# M420X.net
KiCad netlist of a schematic drawn in EAGLE
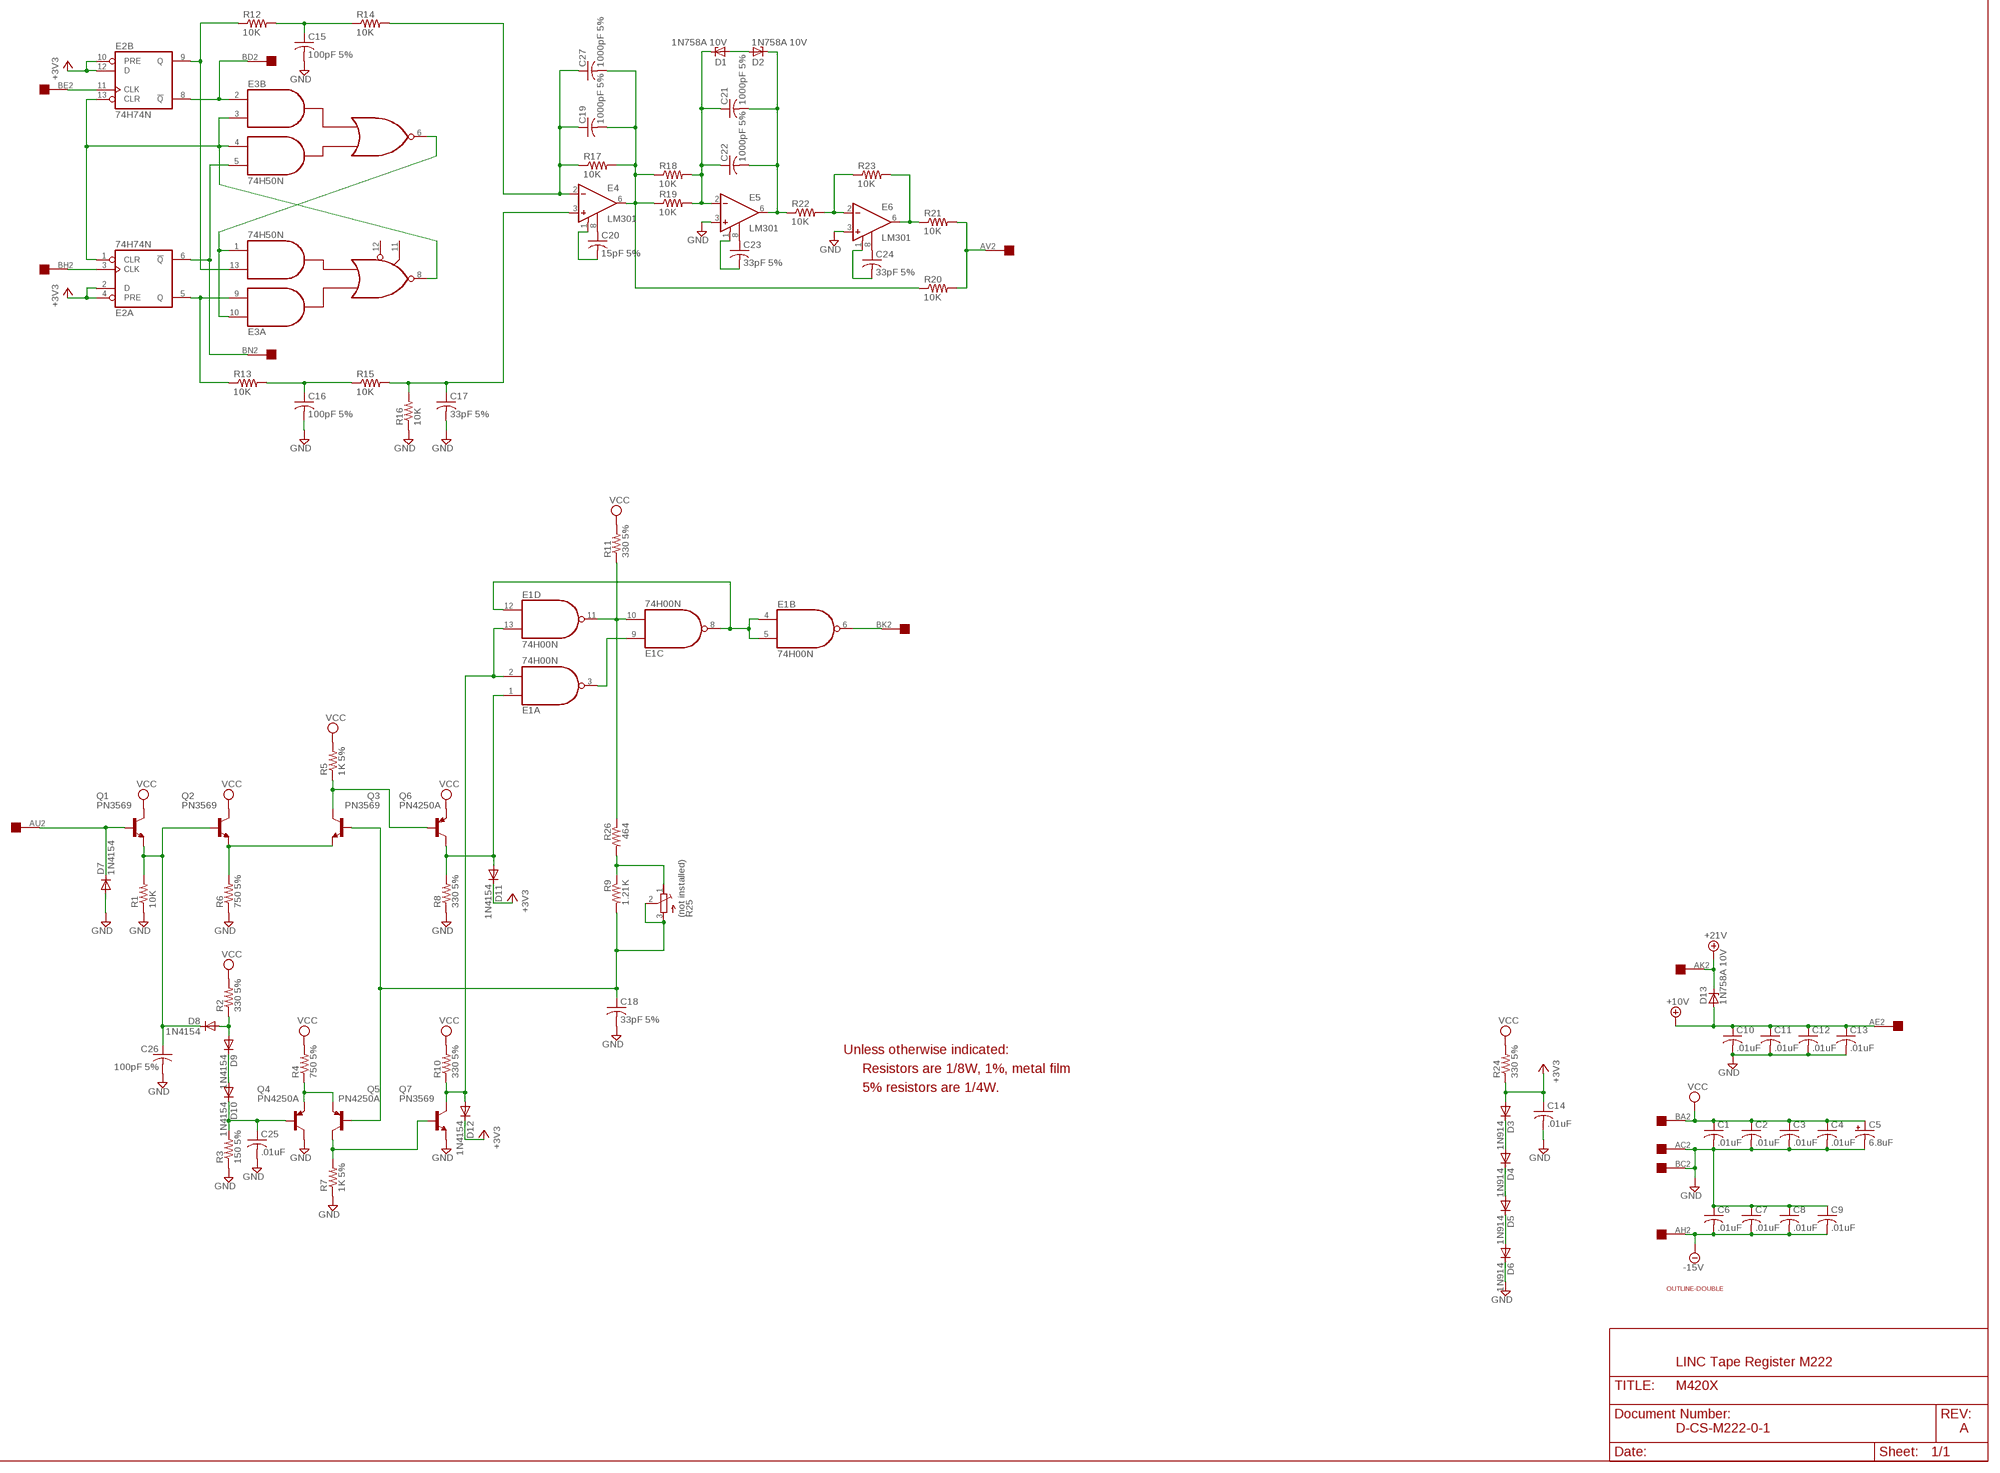
[diagram p0: schematic, sheet 1]

(export (version "E")
  (design (tool "Eeschema 10.0.6"))
  (components
    (comp (ref "C1")
      (value ".01uF")
      (footprint "eagle-import:C050-025X075")
      (libsource (lib "eagle-import") (part "C-US050-025X075"))
    )
    (comp (ref "C2")
      (value ".01uF")
      (footprint "eagle-import:C050-025X075")
      (libsource (lib "eagle-import") (part "C-US050-025X075"))
    )
    (comp (ref "C3")
      (value ".01uF")
      (footprint "eagle-import:C050-025X075")
      (libsource (lib "eagle-import") (part "C-US050-025X075"))
    )
    (comp (ref "C4")
      (value ".01uF")
      (footprint "eagle-import:C050-025X075")
      (libsource (lib "eagle-import") (part "C-US050-025X075"))
    )
    (comp (ref "C5")
      (value "6.8uF")
      (footprint "eagle-import:E12-8")
      (libsource (lib "eagle-import") (part "CPOL-USE20-8AXIAL"))
    )
    (comp (ref "C6")
      (value ".01uF")
      (footprint "eagle-import:C050-025X075")
      (libsource (lib "eagle-import") (part "C-US050-025X075"))
    )
    (comp (ref "C7")
      (value ".01uF")
      (footprint "eagle-import:C050-025X075")
      (libsource (lib "eagle-import") (part "C-US050-025X075"))
    )
    (comp (ref "C8")
      (value ".01uF")
      (footprint "eagle-import:C050-025X075")
      (libsource (lib "eagle-import") (part "C-US050-025X075"))
    )
    (comp (ref "C9")
      (value ".01uF")
      (footprint "eagle-import:C050-025X075")
      (libsource (lib "eagle-import") (part "C-US050-025X075"))
    )
    (comp (ref "C10")
      (value ".01uF")
      (footprint "eagle-import:C050-025X075")
      (libsource (lib "eagle-import") (part "C-US050-025X075"))
    )
    (comp (ref "C11")
      (value ".01uF")
      (footprint "eagle-import:C050-025X075")
      (libsource (lib "eagle-import") (part "C-US050-025X075"))
    )
    (comp (ref "C12")
      (value ".01uF")
      (footprint "eagle-import:C050-025X075")
      (libsource (lib "eagle-import") (part "C-US050-025X075"))
    )
    (comp (ref "C13")
      (value ".01uF")
      (footprint "eagle-import:C050-025X075")
      (libsource (lib "eagle-import") (part "C-US050-025X075"))
    )
    (comp (ref "C14")
      (value ".01uF")
      (footprint "eagle-import:C050-025X075")
      (libsource (lib "eagle-import") (part "C-US050-025X075"))
    )
    (comp (ref "C15")
      (value "100pF 5%")
      (footprint "eagle-import:C050-025X075")
      (libsource (lib "eagle-import") (part "C-US050-025X075"))
    )
    (comp (ref "C16")
      (value "100pF 5%")
      (footprint "eagle-import:C050-025X075")
      (libsource (lib "eagle-import") (part "C-US050-025X075"))
    )
    (comp (ref "C17")
      (value "33pF 5%")
      (footprint "eagle-import:C050-025X075")
      (libsource (lib "eagle-import") (part "C-US050-025X075"))
    )
    (comp (ref "C18")
      (value "33pF 5%")
      (footprint "eagle-import:C050-025X075")
      (libsource (lib "eagle-import") (part "C-US050-025X075"))
    )
    (comp (ref "C19")
      (value "1000pF 5%")
      (footprint "eagle-import:C050-025X075")
      (libsource (lib "eagle-import") (part "C-US050-025X075"))
    )
    (comp (ref "C20")
      (value "15pF 5%")
      (footprint "eagle-import:C050-025X075")
      (libsource (lib "eagle-import") (part "C-US050-025X075"))
    )
    (comp (ref "C21")
      (value "1000pF 5%")
      (footprint "eagle-import:C050-025X075")
      (libsource (lib "eagle-import") (part "C-US050-025X075"))
    )
    (comp (ref "C22")
      (value "1000pF 5%")
      (footprint "eagle-import:C050-025X075")
      (libsource (lib "eagle-import") (part "C-US050-025X075"))
    )
    (comp (ref "C23")
      (value "33pF 5%")
      (footprint "eagle-import:C050-025X075")
      (libsource (lib "eagle-import") (part "C-US050-025X075"))
    )
    (comp (ref "C24")
      (value "33pF 5%")
      (footprint "eagle-import:C050-025X075")
      (libsource (lib "eagle-import") (part "C-US050-025X075"))
    )
    (comp (ref "C25")
      (value ".01uF")
      (footprint "eagle-import:C050-025X075")
      (libsource (lib "eagle-import") (part "C-US050-025X075"))
    )
    (comp (ref "C26")
      (value "100pF 5%")
      (footprint "eagle-import:C050-025X075")
      (libsource (lib "eagle-import") (part "C-US050-025X075"))
    )
    (comp (ref "C27")
      (value "1000pF 5%")
      (footprint "eagle-import:C050-025X075")
      (libsource (lib "eagle-import") (part "C-US050-025X075"))
    )
    (comp (ref "D1")
      (value "1N758A 10V")
      (footprint "eagle-import:DO35Z10")
      (libsource (lib "eagle-import") (part "ZENER-DIODEDO35Z10"))
    )
    (comp (ref "D2")
      (value "1N758A 10V")
      (footprint "eagle-import:DO35Z10")
      (libsource (lib "eagle-import") (part "ZENER-DIODEDO35Z10"))
    )
    (comp (ref "D3")
      (value "1N914")
      (footprint "eagle-import:DO35-10")
      (libsource (lib "eagle-import") (part "1N4148DO35-10"))
    )
    (comp (ref "D4")
      (value "1N914")
      (footprint "eagle-import:DO35-10")
      (libsource (lib "eagle-import") (part "1N4148DO35-10"))
    )
    (comp (ref "D5")
      (value "1N914")
      (footprint "eagle-import:DO35-10")
      (libsource (lib "eagle-import") (part "1N4148DO35-10"))
    )
    (comp (ref "D6")
      (value "1N914")
      (footprint "eagle-import:DO35-10")
      (libsource (lib "eagle-import") (part "1N4148DO35-10"))
    )
    (comp (ref "D7")
      (value "1N4154")
      (footprint "eagle-import:DO35-10")
      (libsource (lib "eagle-import") (part "1N4148DO35-10"))
    )
    (comp (ref "D8")
      (value "1N4154")
      (footprint "eagle-import:DO35-10")
      (libsource (lib "eagle-import") (part "1N4148DO35-10"))
    )
    (comp (ref "D9")
      (value "1N4154")
      (footprint "eagle-import:DO35-10")
      (libsource (lib "eagle-import") (part "1N4148DO35-10"))
    )
    (comp (ref "D10")
      (value "1N4154")
      (footprint "eagle-import:DO35-10")
      (libsource (lib "eagle-import") (part "1N4148DO35-10"))
    )
    (comp (ref "D11")
      (value "1N4154")
      (footprint "eagle-import:DO35-10")
      (libsource (lib "eagle-import") (part "1N4148DO35-10"))
    )
    (comp (ref "D12")
      (value "1N4154")
      (footprint "eagle-import:DO35-10")
      (libsource (lib "eagle-import") (part "1N4148DO35-10"))
    )
    (comp (ref "D13")
      (value "1N758A 10V")
      (footprint "eagle-import:DO35Z10")
      (libsource (lib "eagle-import") (part "ZENER-DIODEDO35Z10"))
    )
    (comp (ref "E1")
      (value "74H00N")
      (footprint "eagle-import:DIL14")
      (libsource (lib "eagle-import") (part "7400N"))
    )
    (comp (ref "E2")
      (value "74H74N")
      (footprint "eagle-import:DIL14")
      (libsource (lib "eagle-import") (part "7474NS"))
    )
    (comp (ref "E3")
      (value "74H50N")
      (footprint "eagle-import:DIL14")
      (libsource (lib "eagle-import") (part "7450N"))
    )
    (comp (ref "E4")
      (value "LM301")
      (footprint "eagle-import:TO99")
      (libsource (lib "eagle-import") (part "LM301"))
    )
    (comp (ref "E5")
      (value "LM301")
      (footprint "eagle-import:TO99")
      (libsource (lib "eagle-import") (part "LM301"))
    )
    (comp (ref "E6")
      (value "LM301")
      (footprint "eagle-import:TO99")
      (libsource (lib "eagle-import") (part "LM301"))
    )
    (comp (ref "Q1")
      (value "PN3569")
      (footprint "eagle-import:TO5")
      (libsource (lib "eagle-import") (part "2N3439"))
    )
    (comp (ref "Q2")
      (value "PN3569")
      (footprint "eagle-import:TO5")
      (libsource (lib "eagle-import") (part "2N3439"))
    )
    (comp (ref "Q3")
      (value "PN3569")
      (footprint "eagle-import:TO5")
      (libsource (lib "eagle-import") (part "2N3439"))
    )
    (comp (ref "Q4")
      (value "PN4250A")
      (footprint "eagle-import:TO39")
      (libsource (lib "eagle-import") (part "2N3635"))
    )
    (comp (ref "Q5")
      (value "PN4250A")
      (footprint "eagle-import:TO39")
      (libsource (lib "eagle-import") (part "2N3635"))
    )
    (comp (ref "Q6")
      (value "PN4250A")
      (footprint "eagle-import:TO39")
      (libsource (lib "eagle-import") (part "2N3635"))
    )
    (comp (ref "Q7")
      (value "PN3569")
      (footprint "eagle-import:TO5")
      (libsource (lib "eagle-import") (part "2N3439"))
    )
    (comp (ref "R1")
      (value "10K")
      (footprint "eagle-import:0207_15")
      (libsource (lib "eagle-import") (part "R-US_0207/15"))
    )
    (comp (ref "R2")
      (value "330 5%")
      (footprint "eagle-import:0207_10")
      (libsource (lib "eagle-import") (part "R-US_0207/10"))
    )
    (comp (ref "R3")
      (value "150 5%")
      (footprint "eagle-import:0207_10")
      (libsource (lib "eagle-import") (part "R-US_0207/10"))
    )
    (comp (ref "R4")
      (value "750 5%")
      (footprint "eagle-import:0207_10")
      (libsource (lib "eagle-import") (part "R-US_0207/10"))
    )
    (comp (ref "R5")
      (value "1K 5%")
      (footprint "eagle-import:0207_10")
      (libsource (lib "eagle-import") (part "R-US_0207/10"))
    )
    (comp (ref "R6")
      (value "750 5%")
      (footprint "eagle-import:0207_10")
      (libsource (lib "eagle-import") (part "R-US_0207/10"))
    )
    (comp (ref "R7")
      (value "1K 5%")
      (footprint "eagle-import:0207_10")
      (libsource (lib "eagle-import") (part "R-US_0207/10"))
    )
    (comp (ref "R8")
      (value "330 5%")
      (footprint "eagle-import:0207_10")
      (libsource (lib "eagle-import") (part "R-US_0207/10"))
    )
    (comp (ref "R9")
      (value "1.21K")
      (footprint "eagle-import:0207_15")
      (libsource (lib "eagle-import") (part "R-US_0207/15"))
    )
    (comp (ref "R10")
      (value "330 5%")
      (footprint "eagle-import:0207_10")
      (libsource (lib "eagle-import") (part "R-US_0207/10"))
    )
    (comp (ref "R11")
      (value "330 5%")
      (footprint "eagle-import:0207_10")
      (libsource (lib "eagle-import") (part "R-US_0207/10"))
    )
    (comp (ref "R12")
      (value "10K")
      (footprint "eagle-import:0207_15")
      (libsource (lib "eagle-import") (part "R-US_0207/15"))
    )
    (comp (ref "R13")
      (value "10K")
      (footprint "eagle-import:0207_15")
      (libsource (lib "eagle-import") (part "R-US_0207/15"))
    )
    (comp (ref "R14")
      (value "10K")
      (footprint "eagle-import:0207_15")
      (libsource (lib "eagle-import") (part "R-US_0207/15"))
    )
    (comp (ref "R15")
      (value "10K")
      (footprint "eagle-import:0207_15")
      (libsource (lib "eagle-import") (part "R-US_0207/15"))
    )
    (comp (ref "R16")
      (value "10K")
      (footprint "eagle-import:0207_15")
      (libsource (lib "eagle-import") (part "R-US_0207/15"))
    )
    (comp (ref "R17")
      (value "10K")
      (footprint "eagle-import:0207_15")
      (libsource (lib "eagle-import") (part "R-US_0207/15"))
    )
    (comp (ref "R18")
      (value "10K")
      (footprint "eagle-import:0207_15")
      (libsource (lib "eagle-import") (part "R-US_0207/15"))
    )
    (comp (ref "R19")
      (value "10K")
      (footprint "eagle-import:0207_15")
      (libsource (lib "eagle-import") (part "R-US_0207/15"))
    )
    (comp (ref "R20")
      (value "10K")
      (footprint "eagle-import:0207_15")
      (libsource (lib "eagle-import") (part "R-US_0207/15"))
    )
    (comp (ref "R21")
      (value "10K")
      (footprint "eagle-import:0207_15")
      (libsource (lib "eagle-import") (part "R-US_0207/15"))
    )
    (comp (ref "R22")
      (value "10K")
      (footprint "eagle-import:0207_15")
      (libsource (lib "eagle-import") (part "R-US_0207/15"))
    )
    (comp (ref "R23")
      (value "10K")
      (footprint "eagle-import:0207_15")
      (libsource (lib "eagle-import") (part "R-US_0207/15"))
    )
    (comp (ref "R24")
      (value "330 5%")
      (footprint "eagle-import:0207_10")
      (libsource (lib "eagle-import") (part "R-US_0207/10"))
    )
    (comp (ref "R25")
      (value "(not installed)")
      (footprint "eagle-import:3006Y")
      (libsource (lib "eagle-import") (part "275P"))
    )
    (comp (ref "R26")
      (value "464")
      (footprint "eagle-import:0207_15")
      (libsource (lib "eagle-import") (part "R-US_0207/15"))
    )
    (comp (ref "U$1")
      (value "DOUBLE")
      (footprint "eagle-import:EDGE-CON4")
      (libsource (lib "eagle-import") (part "DOUBLE"))
    )
    (comp (ref "U$2")
      (value "OUTLINE-DOUBLE")
      (footprint "eagle-import:DOUBLE")
      (libsource (lib "eagle-import") (part "OUTLINE-DOUBLE"))
    )
  )
  (nets
    (net (code "1") (name "+3V3") (class "Default")
      (node (ref "C14") (pin "1") (pinfunction "1_1") (pintype "passive"))
      (node (ref "D11") (pin "C") (pinfunction "C_C") (pintype "passive"))
      (node (ref "D12") (pin "C") (pinfunction "C_C") (pintype "passive"))
      (node (ref "D3") (pin "A") (pinfunction "A_A") (pintype "passive"))
      (node (ref "E2") (pin "10") (pinfunction "PRE_10") (pintype "input"))
      (node (ref "E2") (pin "12") (pinfunction "D_12") (pintype "input"))
      (node (ref "E2") (pin "2") (pinfunction "D_2") (pintype "input"))
      (node (ref "E2") (pin "4") (pinfunction "PRE_4") (pintype "input"))
      (node (ref "R24") (pin "1") (pinfunction "1_1") (pintype "passive"))
    )
    (net (code "2") (name "+10V") (class "Default")
      (node (ref "C10") (pin "1") (pinfunction "1_1") (pintype "passive"))
      (node (ref "C11") (pin "1") (pinfunction "1_1") (pintype "passive"))
      (node (ref "C12") (pin "1") (pinfunction "1_1") (pintype "passive"))
      (node (ref "C13") (pin "1") (pinfunction "1_1") (pintype "passive"))
      (node (ref "D13") (pin "A") (pinfunction "A_A") (pintype "passive"))
      (node (ref "U$1") (pin "AE2") (pinfunction "1_AE2") (pintype "bidirectional"))
    )
    (net (code "3") (name "+21V") (class "Default")
      (node (ref "D13") (pin "C") (pinfunction "C_C") (pintype "passive"))
      (node (ref "U$1") (pin "AK2") (pinfunction "1_AK2") (pintype "bidirectional"))
    )
    (net (code "4") (name "-15V") (class "Default")
      (node (ref "C6") (pin "2") (pinfunction "2_2") (pintype "passive"))
      (node (ref "C7") (pin "2") (pinfunction "2_2") (pintype "passive"))
      (node (ref "C8") (pin "2") (pinfunction "2_2") (pintype "passive"))
      (node (ref "C9") (pin "2") (pinfunction "2_2") (pintype "passive"))
      (node (ref "U$1") (pin "AH2") (pinfunction "1_AH2") (pintype "bidirectional"))
    )
    (net (code "5") (name "GND") (class "Default")
      (node (ref "C1") (pin "2") (pinfunction "2_2") (pintype "passive"))
      (node (ref "C10") (pin "2") (pinfunction "2_2") (pintype "passive"))
      (node (ref "C11") (pin "2") (pinfunction "2_2") (pintype "passive"))
      (node (ref "C12") (pin "2") (pinfunction "2_2") (pintype "passive"))
      (node (ref "C13") (pin "2") (pinfunction "2_2") (pintype "passive"))
      (node (ref "C14") (pin "2") (pinfunction "2_2") (pintype "passive"))
      (node (ref "C15") (pin "2") (pinfunction "2_2") (pintype "passive"))
      (node (ref "C16") (pin "2") (pinfunction "2_2") (pintype "passive"))
      (node (ref "C17") (pin "2") (pinfunction "2_2") (pintype "passive"))
      (node (ref "C18") (pin "2") (pinfunction "2_2") (pintype "passive"))
      (node (ref "C2") (pin "2") (pinfunction "2_2") (pintype "passive"))
      (node (ref "C25") (pin "2") (pinfunction "2_2") (pintype "passive"))
      (node (ref "C26") (pin "2") (pinfunction "2_2") (pintype "passive"))
      (node (ref "C3") (pin "2") (pinfunction "2_2") (pintype "passive"))
      (node (ref "C4") (pin "2") (pinfunction "2_2") (pintype "passive"))
      (node (ref "C5") (pin "-") (pinfunction "-_-") (pintype "passive"))
      (node (ref "C6") (pin "1") (pinfunction "1_1") (pintype "passive"))
      (node (ref "C7") (pin "1") (pinfunction "1_1") (pintype "passive"))
      (node (ref "C8") (pin "1") (pinfunction "1_1") (pintype "passive"))
      (node (ref "C9") (pin "1") (pinfunction "1_1") (pintype "passive"))
      (node (ref "D6") (pin "C") (pinfunction "C_C") (pintype "passive"))
      (node (ref "D7") (pin "A") (pinfunction "A_A") (pintype "passive"))
      (node (ref "E5") (pin "3") (pinfunction "+IN_3") (pintype "input"))
      (node (ref "E6") (pin "3") (pinfunction "+IN_3") (pintype "input"))
      (node (ref "Q4") (pin "3") (pinfunction "C_3") (pintype "passive"))
      (node (ref "Q7") (pin "1") (pinfunction "E_1") (pintype "passive"))
      (node (ref "R1") (pin "1") (pinfunction "1_1") (pintype "passive"))
      (node (ref "R16") (pin "1") (pinfunction "1_1") (pintype "passive"))
      (node (ref "R3") (pin "1") (pinfunction "1_1") (pintype "passive"))
      (node (ref "R6") (pin "1") (pinfunction "1_1") (pintype "passive"))
      (node (ref "R7") (pin "1") (pinfunction "1_1") (pintype "passive"))
      (node (ref "R8") (pin "1") (pinfunction "1_1") (pintype "passive"))
      (node (ref "U$1") (pin "AC2") (pinfunction "1_AC2") (pintype "bidirectional"))
      (node (ref "U$1") (pin "BC2") (pinfunction "1_BC2") (pintype "bidirectional"))
    )
    (net (code "6") (name "Net-(C15-Pad1)") (class "Default")
      (node (ref "C15") (pin "1") (pinfunction "1_1") (pintype "passive"))
      (node (ref "R12") (pin "2") (pinfunction "2_2") (pintype "passive"))
      (node (ref "R14") (pin "1") (pinfunction "1_1") (pintype "passive"))
    )
    (net (code "7") (name "Net-(C16-Pad1)") (class "Default")
      (node (ref "C16") (pin "1") (pinfunction "1_1") (pintype "passive"))
      (node (ref "R13") (pin "2") (pinfunction "2_2") (pintype "passive"))
      (node (ref "R15") (pin "1") (pinfunction "1_1") (pintype "passive"))
    )
    (net (code "8") (name "Net-(D1-PadA)") (class "Default")
      (node (ref "D1") (pin "A") (pinfunction "A_A") (pintype "passive"))
      (node (ref "D2") (pin "A") (pinfunction "A_A") (pintype "passive"))
    )
    (net (code "9") (name "Net-(D3-PadC)") (class "Default")
      (node (ref "D3") (pin "C") (pinfunction "C_C") (pintype "passive"))
      (node (ref "D4") (pin "A") (pinfunction "A_A") (pintype "passive"))
    )
    (net (code "10") (name "Net-(D4-PadC)") (class "Default")
      (node (ref "D4") (pin "C") (pinfunction "C_C") (pintype "passive"))
      (node (ref "D5") (pin "A") (pinfunction "A_A") (pintype "passive"))
    )
    (net (code "11") (name "Net-(D5-PadC)") (class "Default")
      (node (ref "D5") (pin "C") (pinfunction "C_C") (pintype "passive"))
      (node (ref "D6") (pin "A") (pinfunction "A_A") (pintype "passive"))
    )
    (net (code "12") (name "Net-(D8-PadA)") (class "Default")
      (node (ref "D8") (pin "A") (pinfunction "A_A") (pintype "passive"))
      (node (ref "D9") (pin "A") (pinfunction "A_A") (pintype "passive"))
      (node (ref "R2") (pin "1") (pinfunction "1_1") (pintype "passive"))
    )
    (net (code "13") (name "Net-(D10-PadA)") (class "Default")
      (node (ref "D10") (pin "A") (pinfunction "A_A") (pintype "passive"))
      (node (ref "D9") (pin "C") (pinfunction "C_C") (pintype "passive"))
    )
    (net (code "14") (name "Net-(E1A-I0)") (class "Default")
      (node (ref "D11") (pin "A") (pinfunction "A_A") (pintype "passive"))
      (node (ref "E1") (pin "1") (pinfunction "I0_1") (pintype "input"))
      (node (ref "Q6") (pin "3") (pinfunction "C_3") (pintype "passive"))
      (node (ref "R8") (pin "2") (pinfunction "2_2") (pintype "passive"))
    )
    (net (code "15") (name "Net-(E1A-I1)") (class "Default")
      (node (ref "D12") (pin "A") (pinfunction "A_A") (pintype "passive"))
      (node (ref "E1") (pin "13") (pinfunction "I1_13") (pintype "input"))
      (node (ref "E1") (pin "2") (pinfunction "I1_2") (pintype "input"))
      (node (ref "Q7") (pin "3") (pinfunction "C_3") (pintype "passive"))
      (node (ref "R10") (pin "1") (pinfunction "1_1") (pintype "passive"))
    )
    (net (code "16") (name "Net-(E1A-O)") (class "Default")
      (node (ref "E1") (pin "3") (pinfunction "O_3") (pintype "output"))
      (node (ref "E1") (pin "9") (pinfunction "I0_9") (pintype "input"))
    )
    (net (code "17") (name "Net-(E1B-I0)") (class "Default")
      (node (ref "E1") (pin "12") (pinfunction "I0_12") (pintype "input"))
      (node (ref "E1") (pin "4") (pinfunction "I0_4") (pintype "input"))
      (node (ref "E1") (pin "5") (pinfunction "I1_5") (pintype "input"))
      (node (ref "E1") (pin "8") (pinfunction "O_8") (pintype "output"))
    )
    (net (code "18") (name "Net-(E1B-O)") (class "Default")
      (node (ref "E1") (pin "6") (pinfunction "O_6") (pintype "output"))
      (node (ref "U$1") (pin "BK2") (pinfunction "1_BK2") (pintype "bidirectional"))
    )
    (net (code "19") (name "Net-(E1C-I1)") (class "Default")
      (node (ref "E1") (pin "10") (pinfunction "I1_10") (pintype "input"))
      (node (ref "E1") (pin "11") (pinfunction "O_11") (pintype "output"))
      (node (ref "R11") (pin "1") (pinfunction "1_1") (pintype "passive"))
      (node (ref "R26") (pin "1") (pinfunction "1_1") (pintype "passive"))
    )
    (net (code "20") (name "Net-(E2A-CLK)") (class "Default")
      (node (ref "E2") (pin "3") (pinfunction "CLK_3") (pintype "input"))
      (node (ref "U$1") (pin "BH2") (pinfunction "1_BH2") (pintype "bidirectional"))
    )
    (net (code "21") (name "Net-(E2A-CLR)") (class "Default")
      (node (ref "E2") (pin "1") (pinfunction "CLR_1") (pintype "input"))
      (node (ref "E2") (pin "13") (pinfunction "CLR_13") (pintype "input"))
      (node (ref "E3") (pin "3") (pinfunction "I2_3") (pintype "input"))
      (node (ref "E3") (pin "4") (pinfunction "I3_4") (pintype "input"))
      (node (ref "E3") (pin "8") (pinfunction "O_8") (pintype "output"))
    )
    (net (code "22") (name "Net-(E2A-Q)") (class "Default")
      (node (ref "E2") (pin "5") (pinfunction "Q_5") (pintype "output"))
      (node (ref "E3") (pin "9") (pinfunction "I2_9") (pintype "input"))
      (node (ref "R13") (pin "1") (pinfunction "1_1") (pintype "passive"))
    )
    (net (code "23") (name "Net-(E2A-~{Q})") (class "Default")
      (node (ref "E2") (pin "6") (pinfunction "~{Q}_6") (pintype "output"))
      (node (ref "E3") (pin "5") (pinfunction "I4_5") (pintype "input"))
      (node (ref "U$1") (pin "BN2") (pinfunction "1_BN2") (pintype "bidirectional"))
    )
    (net (code "24") (name "Net-(E2B-CLK)") (class "Default")
      (node (ref "E2") (pin "11") (pinfunction "CLK_11") (pintype "input"))
      (node (ref "U$1") (pin "BE2") (pinfunction "1_BE2") (pintype "bidirectional"))
    )
    (net (code "25") (name "Net-(E2B-Q)") (class "Default")
      (node (ref "E2") (pin "9") (pinfunction "Q_9") (pintype "output"))
      (node (ref "E3") (pin "13") (pinfunction "I3_13") (pintype "input"))
      (node (ref "R12") (pin "1") (pinfunction "1_1") (pintype "passive"))
    )
    (net (code "26") (name "Net-(E2B-~{Q})") (class "Default")
      (node (ref "E2") (pin "8") (pinfunction "~{Q}_8") (pintype "output"))
      (node (ref "E3") (pin "2") (pinfunction "I1_2") (pintype "input"))
      (node (ref "U$1") (pin "BD2") (pinfunction "1_BD2") (pintype "bidirectional"))
    )
    (net (code "27") (name "Net-(E3A-I1)") (class "Default")
      (node (ref "E3") (pin "1") (pinfunction "I4_1") (pintype "input"))
      (node (ref "E3") (pin "10") (pinfunction "I1_10") (pintype "input"))
      (node (ref "E3") (pin "6") (pinfunction "O_6") (pintype "output"))
    )
    (net (code "28") (name "Net-(E4A-+IN)") (class "Default")
      (node (ref "C17") (pin "1") (pinfunction "1_1") (pintype "passive"))
      (node (ref "E4") (pin "3") (pinfunction "+IN_3") (pintype "input"))
      (node (ref "R15") (pin "2") (pinfunction "2_2") (pintype "passive"))
      (node (ref "R16") (pin "2") (pinfunction "2_2") (pintype "passive"))
    )
    (net (code "29") (name "Net-(E4A--IN)") (class "Default")
      (node (ref "C19") (pin "1") (pinfunction "1_1") (pintype "passive"))
      (node (ref "C27") (pin "1") (pinfunction "1_1") (pintype "passive"))
      (node (ref "E4") (pin "2") (pinfunction "-IN_2") (pintype "input"))
      (node (ref "R14") (pin "2") (pinfunction "2_2") (pintype "passive"))
      (node (ref "R17") (pin "1") (pinfunction "1_1") (pintype "passive"))
    )
    (net (code "30") (name "Net-(E4A-CMP)") (class "Default")
      (node (ref "C20") (pin "1") (pinfunction "1_1") (pintype "passive"))
      (node (ref "E4") (pin "8") (pinfunction "CMP_8") (pintype "passive"))
    )
    (net (code "31") (name "Net-(E4A-ON{slash}CMP)") (class "Default")
      (node (ref "C20") (pin "2") (pinfunction "2_2") (pintype "passive"))
      (node (ref "E4") (pin "1") (pinfunction "ON/CMP_1") (pintype "passive"))
    )
    (net (code "32") (name "Net-(E4A-OUT)") (class "Default")
      (node (ref "C19") (pin "2") (pinfunction "2_2") (pintype "passive"))
      (node (ref "C27") (pin "2") (pinfunction "2_2") (pintype "passive"))
      (node (ref "E4") (pin "6") (pinfunction "OUT_6") (pintype "output"))
      (node (ref "R17") (pin "2") (pinfunction "2_2") (pintype "passive"))
      (node (ref "R18") (pin "1") (pinfunction "1_1") (pintype "passive"))
      (node (ref "R19") (pin "1") (pinfunction "1_1") (pintype "passive"))
      (node (ref "R20") (pin "1") (pinfunction "1_1") (pintype "passive"))
    )
    (net (code "33") (name "Net-(E5A--IN)") (class "Default")
      (node (ref "C21") (pin "1") (pinfunction "1_1") (pintype "passive"))
      (node (ref "C22") (pin "1") (pinfunction "1_1") (pintype "passive"))
      (node (ref "D1") (pin "C") (pinfunction "C_C") (pintype "passive"))
      (node (ref "E5") (pin "2") (pinfunction "-IN_2") (pintype "input"))
      (node (ref "R18") (pin "2") (pinfunction "2_2") (pintype "passive"))
      (node (ref "R19") (pin "2") (pinfunction "2_2") (pintype "passive"))
    )
    (net (code "34") (name "Net-(E5A-CMP)") (class "Default")
      (node (ref "C23") (pin "1") (pinfunction "1_1") (pintype "passive"))
      (node (ref "E5") (pin "8") (pinfunction "CMP_8") (pintype "passive"))
    )
    (net (code "35") (name "Net-(E5A-ON{slash}CMP)") (class "Default")
      (node (ref "C23") (pin "2") (pinfunction "2_2") (pintype "passive"))
      (node (ref "E5") (pin "1") (pinfunction "ON/CMP_1") (pintype "passive"))
    )
    (net (code "36") (name "Net-(E5A-OUT)") (class "Default")
      (node (ref "C21") (pin "2") (pinfunction "2_2") (pintype "passive"))
      (node (ref "C22") (pin "2") (pinfunction "2_2") (pintype "passive"))
      (node (ref "D2") (pin "C") (pinfunction "C_C") (pintype "passive"))
      (node (ref "E5") (pin "6") (pinfunction "OUT_6") (pintype "output"))
      (node (ref "R22") (pin "1") (pinfunction "1_1") (pintype "passive"))
    )
    (net (code "37") (name "Net-(E6A--IN)") (class "Default")
      (node (ref "E6") (pin "2") (pinfunction "-IN_2") (pintype "input"))
      (node (ref "R22") (pin "2") (pinfunction "2_2") (pintype "passive"))
      (node (ref "R23") (pin "1") (pinfunction "1_1") (pintype "passive"))
    )
    (net (code "38") (name "Net-(E6A-CMP)") (class "Default")
      (node (ref "C24") (pin "1") (pinfunction "1_1") (pintype "passive"))
      (node (ref "E6") (pin "8") (pinfunction "CMP_8") (pintype "passive"))
    )
    (net (code "39") (name "Net-(E6A-ON{slash}CMP)") (class "Default")
      (node (ref "C24") (pin "2") (pinfunction "2_2") (pintype "passive"))
      (node (ref "E6") (pin "1") (pinfunction "ON/CMP_1") (pintype "passive"))
    )
    (net (code "40") (name "Net-(E6A-OUT)") (class "Default")
      (node (ref "E6") (pin "6") (pinfunction "OUT_6") (pintype "output"))
      (node (ref "R21") (pin "1") (pinfunction "1_1") (pintype "passive"))
      (node (ref "R23") (pin "2") (pinfunction "2_2") (pintype "passive"))
    )
    (net (code "41") (name "Net-(Q1-B)") (class "Default")
      (node (ref "D7") (pin "C") (pinfunction "C_C") (pintype "passive"))
      (node (ref "Q1") (pin "2") (pinfunction "B_2") (pintype "passive"))
      (node (ref "U$1") (pin "AU2") (pinfunction "1_AU2") (pintype "bidirectional"))
    )
    (net (code "42") (name "Net-(Q1-E)") (class "Default")
      (node (ref "C26") (pin "1") (pinfunction "1_1") (pintype "passive"))
      (node (ref "D8") (pin "C") (pinfunction "C_C") (pintype "passive"))
      (node (ref "Q1") (pin "1") (pinfunction "E_1") (pintype "passive"))
      (node (ref "Q2") (pin "2") (pinfunction "B_2") (pintype "passive"))
      (node (ref "R1") (pin "2") (pinfunction "2_2") (pintype "passive"))
    )
    (net (code "43") (name "Net-(Q2-E)") (class "Default")
      (node (ref "Q2") (pin "1") (pinfunction "E_1") (pintype "passive"))
      (node (ref "Q3") (pin "1") (pinfunction "E_1") (pintype "passive"))
      (node (ref "R6") (pin "2") (pinfunction "2_2") (pintype "passive"))
    )
    (net (code "44") (name "Net-(Q3-B)") (class "Default")
      (node (ref "C18") (pin "1") (pinfunction "1_1") (pintype "passive"))
      (node (ref "Q3") (pin "2") (pinfunction "B_2") (pintype "passive"))
      (node (ref "Q5") (pin "2") (pinfunction "B_2") (pintype "passive"))
      (node (ref "R25") (pin "2") (pinfunction "S_2") (pintype "passive"))
      (node (ref "R25") (pin "3") (pinfunction "E_3") (pintype "passive"))
      (node (ref "R9") (pin "2") (pinfunction "2_2") (pintype "passive"))
    )
    (net (code "45") (name "Net-(Q3-C)") (class "Default")
      (node (ref "Q3") (pin "3") (pinfunction "C_3") (pintype "passive"))
      (node (ref "Q6") (pin "2") (pinfunction "B_2") (pintype "passive"))
      (node (ref "R5") (pin "1") (pinfunction "1_1") (pintype "passive"))
    )
    (net (code "46") (name "Net-(Q4-B)") (class "Default")
      (node (ref "C25") (pin "1") (pinfunction "1_1") (pintype "passive"))
      (node (ref "D10") (pin "C") (pinfunction "C_C") (pintype "passive"))
      (node (ref "Q4") (pin "2") (pinfunction "B_2") (pintype "passive"))
      (node (ref "R3") (pin "2") (pinfunction "2_2") (pintype "passive"))
    )
    (net (code "47") (name "Net-(Q4-E)") (class "Default")
      (node (ref "Q4") (pin "1") (pinfunction "E_1") (pintype "passive"))
      (node (ref "Q5") (pin "1") (pinfunction "E_1") (pintype "passive"))
      (node (ref "R4") (pin "1") (pinfunction "1_1") (pintype "passive"))
    )
    (net (code "48") (name "Net-(Q5-C)") (class "Default")
      (node (ref "Q5") (pin "3") (pinfunction "C_3") (pintype "passive"))
      (node (ref "Q7") (pin "2") (pinfunction "B_2") (pintype "passive"))
      (node (ref "R7") (pin "2") (pinfunction "2_2") (pintype "passive"))
    )
    (net (code "49") (name "Net-(R25-A)") (class "Default")
      (node (ref "R25") (pin "1") (pinfunction "A_1") (pintype "passive"))
      (node (ref "R26") (pin "2") (pinfunction "2_2") (pintype "passive"))
      (node (ref "R9") (pin "1") (pinfunction "1_1") (pintype "passive"))
    )
    (net (code "50") (name "Net-(U$1AJ-1)") (class "Default")
      (node (ref "R20") (pin "2") (pinfunction "2_2") (pintype "passive"))
      (node (ref "R21") (pin "2") (pinfunction "2_2") (pintype "passive"))
      (node (ref "U$1") (pin "AV2") (pinfunction "1_AV2") (pintype "bidirectional"))
    )
    (net (code "51") (name "VCC") (class "Default")
      (node (ref "C1") (pin "1") (pinfunction "1_1") (pintype "passive"))
      (node (ref "C2") (pin "1") (pinfunction "1_1") (pintype "passive"))
      (node (ref "C3") (pin "1") (pinfunction "1_1") (pintype "passive"))
      (node (ref "C4") (pin "1") (pinfunction "1_1") (pintype "passive"))
      (node (ref "C5") (pin "+") (pinfunction "+_+") (pintype "passive"))
      (node (ref "Q1") (pin "3") (pinfunction "C_3") (pintype "passive"))
      (node (ref "Q2") (pin "3") (pinfunction "C_3") (pintype "passive"))
      (node (ref "Q6") (pin "1") (pinfunction "E_1") (pintype "passive"))
      (node (ref "R10") (pin "2") (pinfunction "2_2") (pintype "passive"))
      (node (ref "R11") (pin "2") (pinfunction "2_2") (pintype "passive"))
      (node (ref "R2") (pin "2") (pinfunction "2_2") (pintype "passive"))
      (node (ref "R24") (pin "2") (pinfunction "2_2") (pintype "passive"))
      (node (ref "R4") (pin "2") (pinfunction "2_2") (pintype "passive"))
      (node (ref "R5") (pin "2") (pinfunction "2_2") (pintype "passive"))
      (node (ref "U$1") (pin "BA2") (pinfunction "1_BA2") (pintype "bidirectional"))
    )
    (net (code "52") (name "unconnected-(E3A-I5-Pad12)") (class "Default")
      (node (ref "E3") (pin "12") (pinfunction "I5_12") (pintype "passive"))
    )
    (net (code "53") (name "unconnected-(E3A-I6-Pad11)") (class "Default")
      (node (ref "E3") (pin "11") (pinfunction "I6_11") (pintype "passive"))
    )
  )
)
